# PROC010C_LDO.net
KiCad netlist of a schematic drawn in Altium Designer
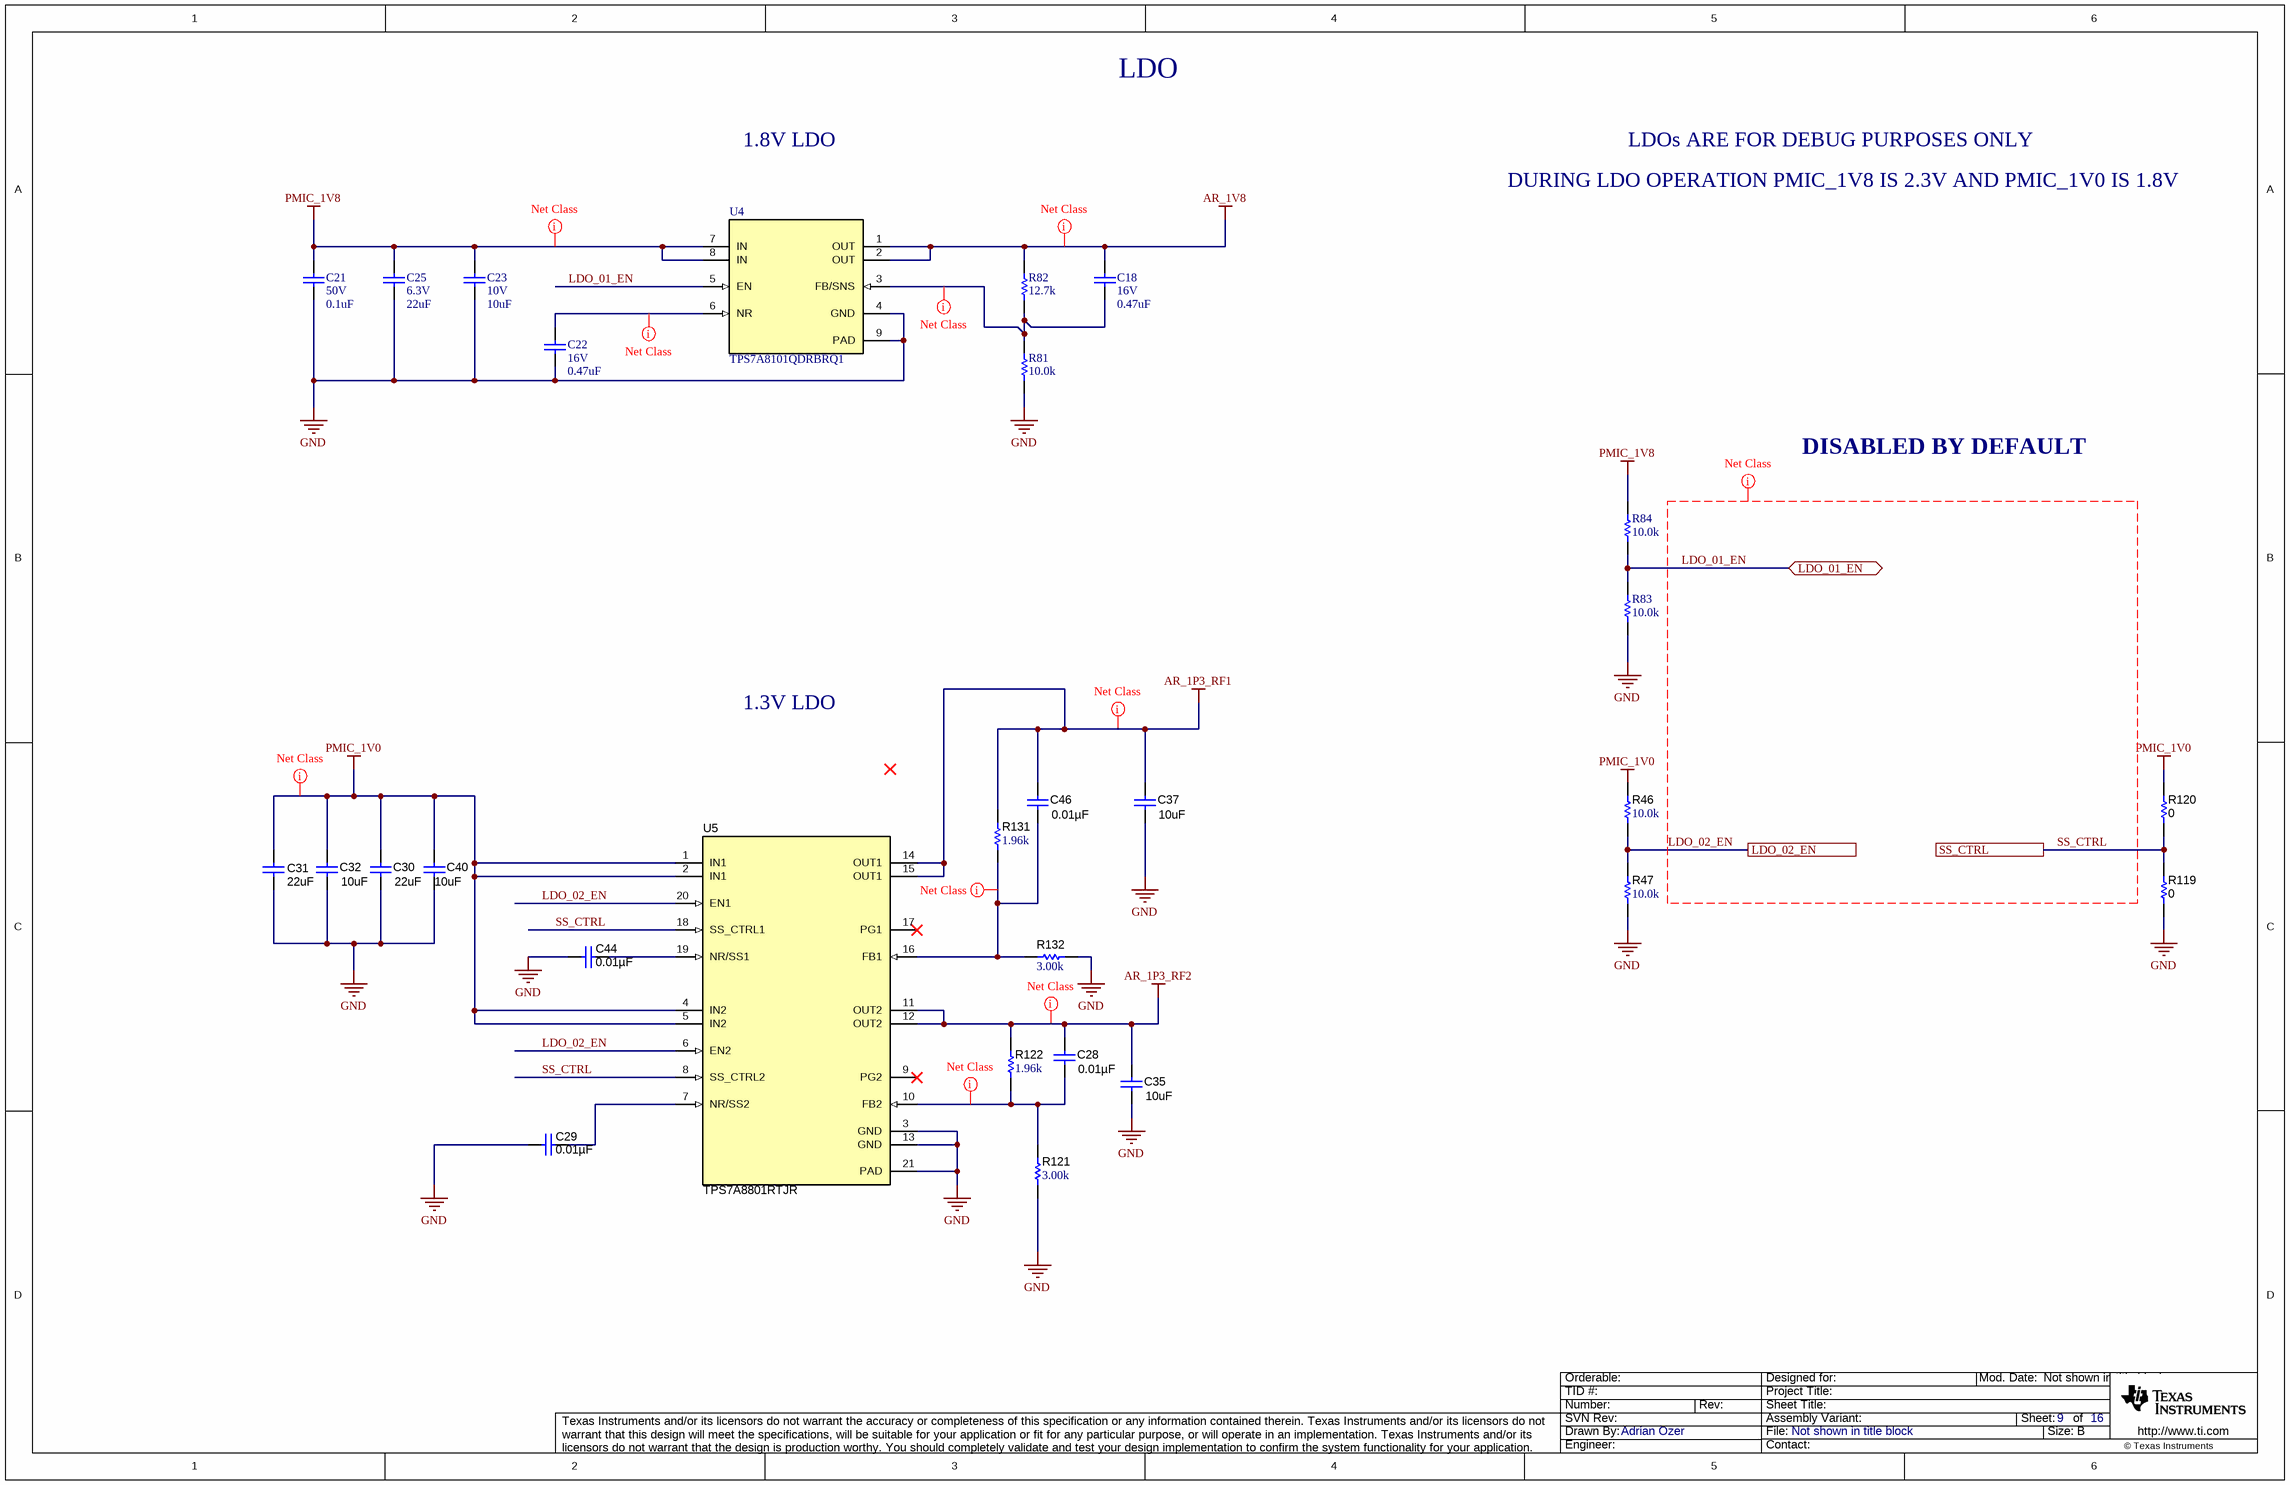
[diagram p0: PROC010C_LDO.SchDoc]

(export (version "E")
  (design (tool "Eeschema 10.0.6"))
  (components
    (comp (ref "C18")
      (value "GCM188R71C474KA55D")
      (footprint "0603")
      (description "CAP, CERM, 0.47 uF, 16 V, +/- 10%, X7R, AEC-Q200 Grade 1, 0603")
      (fields
        (field (name "MANUFACTURER") "MuRata")
        (field (name "VDC_V") "16V")
        (field (name "VALUEDISPLAYED") "0.47uF")
        (field (name "PUBLISHER") "Texas Instruments")
      )
      (libsource (lib "Altium Vault - TI") (part "Capacitor"))
    )
    (comp (ref "C21")
      (value "CGA2B3X7R1H104K050BB")
      (footprint "0402")
      (description "CAP, CERM, 0.1 uF, 50 V, +/- 10%, X7R, AEC-Q200 Grade 1, 0402")
      (fields
        (field (name "MANUFACTURER") "TDK")
        (field (name "VDC_V") "50V")
        (field (name "VALUEDISPLAYED") "0.1uF")
        (field (name "PUBLISHER") "Texas Instruments")
      )
      (libsource (lib "Altium Vault - TI") (part "Capacitor"))
    )
    (comp (ref "C22")
      (value "GCM188R71C474KA55D")
      (footprint "0603")
      (description "CAP, CERM, 0.47 uF, 16 V, +/- 10%, X7R, AEC-Q200 Grade 1, 0603")
      (fields
        (field (name "MANUFACTURER") "MuRata")
        (field (name "VDC_V") "16V")
        (field (name "VALUEDISPLAYED") "0.47uF")
        (field (name "PUBLISHER") "Texas Instruments")
      )
      (libsource (lib "Altium Vault - TI") (part "Capacitor"))
    )
    (comp (ref "C23")
      (value "GCM21BR71A106KE22L")
      (footprint "0805_HV")
      (description "CAP, CERM, 10 uF, 10 V, +/- 10%, X7R, 0805")
      (fields
        (field (name "MANUFACTURER") "MuRata")
        (field (name "VDC_V") "10V")
        (field (name "VALUEDISPLAYED") "10uF")
        (field (name "PUBLISHER") "Texas Instruments")
      )
      (libsource (lib "Altium Vault - TI") (part "Capacitor"))
    )
    (comp (ref "C25")
      (value "CGA5L1X7R0J226M160AC")
      (footprint "1206_180")
      (description "CAP, CERM, 22 uF, 6.3 V, +/- 10%, X7R, AEC-Q200 Grade 1, 1206")
      (fields
        (field (name "MANUFACTURER") "TDK")
        (field (name "VDC_V") "6.3V")
        (field (name "VALUEDISPLAYED") "22uF")
        (field (name "PUBLISHER") "Texas Instruments")
      )
      (libsource (lib "Altium Vault - TI") (part "Capacitor"))
    )
    (comp (ref "C28")
      (value "CGA2B3X8R1H103K050BB")
      (footprint "0402L")
      (description "CAP, CERM, 0.01 µF, 50 V,+/- 10%, X8R, AEC-Q200 Grade 0, 0402")
      (fields (field (name "MANUFACTURER") "TDK") (field (name "VALUEDISPLAYED") "0.01µF"))
      (libsource (lib "Altium Vault - TI") (part "Capacitor"))
    )
    (comp (ref "C29")
      (value "CGA2B3X8R1H103K050BB")
      (footprint "0402L")
      (description "CAP, CERM, 0.01 µF, 50 V,+/- 10%, X8R, AEC-Q200 Grade 0, 0402")
      (fields (field (name "MANUFACTURER") "TDK") (field (name "VALUEDISPLAYED") "0.01µF"))
      (libsource (lib "Altium Vault - TI") (part "Capacitor"))
    )
    (comp (ref "C30")
      (value "CGA5L1X7R0J226M160AC")
      (footprint "1206_180")
      (description "CAP, CERM, 22 uF, 6.3 V, +/- 10%, X7R, AEC-Q200 Grade 1, 1206")
      (fields
        (field (name "MANUFACTURER") "TDK")
        (field (name "VALUEDISPLAYED") "22uF")
        (field (name "PUBLISHER") "Texas Instruments")
      )
      (libsource (lib "Altium Vault - TI") (part "Capacitor"))
    )
    (comp (ref "C31")
      (value "CGA5L1X7R0J226M160AC")
      (footprint "1206_180")
      (description "CAP, CERM, 22 uF, 6.3 V, +/- 10%, X7R, AEC-Q200 Grade 1, 1206")
      (fields
        (field (name "MANUFACTURER") "TDK")
        (field (name "VALUEDISPLAYED") "22uF")
        (field (name "PUBLISHER") "Texas Instruments")
      )
      (libsource (lib "Altium Vault - TI") (part "Capacitor"))
    )
    (comp (ref "C32")
      (value "GCM21BR71A106KE22L")
      (footprint "0805")
      (description "CAP, CERM, 10 uF, 10 V, +/- 10%, X7R, 0805")
      (fields
        (field (name "MANUFACTURER") "MuRata")
        (field (name "VALUEDISPLAYED") "10uF")
        (field (name "PUBLISHER") "Texas Instruments")
      )
      (libsource (lib "Altium Vault - TI") (part "CMP-0008017-2"))
    )
    (comp (ref "C35")
      (value "GCM21BR71A106KE22L")
      (footprint "0805_HV")
      (description "CAP, CERM, 10 uF, 10 V, +/- 10%, X7R, 0805")
      (fields
        (field (name "MANUFACTURER") "MuRata")
        (field (name "VALUEDISPLAYED") "10uF")
        (field (name "PUBLISHER") "Texas Instruments")
      )
      (libsource (lib "Altium Vault - TI") (part "CMP-0008017-2"))
    )
    (comp (ref "C37")
      (value "GCM21BR71A106KE22L")
      (footprint "0805_HV")
      (description "CAP, CERM, 10 uF, 10 V, +/- 10%, X7R, 0805")
      (fields
        (field (name "MANUFACTURER") "MuRata")
        (field (name "VALUEDISPLAYED") "10uF")
        (field (name "PUBLISHER") "Texas Instruments")
      )
      (libsource (lib "Altium Vault - TI") (part "CMP-0008017-2"))
    )
    (comp (ref "C40")
      (value "GCM21BR71A106KE22L")
      (footprint "0805_HV1")
      (description "CAP, CERM, 10 uF, 10 V, +/- 10%, X7R, 0805")
      (fields
        (field (name "MANUFACTURER") "MuRata")
        (field (name "VALUEDISPLAYED") "10uF")
        (field (name "PUBLISHER") "Texas Instruments")
      )
      (libsource (lib "Altium Vault - TI") (part "CMP-0008017-2"))
    )
    (comp (ref "C44")
      (value "CGA2B3X8R1H103K050BB")
      (footprint "0402L")
      (description "CAP, CERM, 0.01 µF, 50 V,+/- 10%, X8R, AEC-Q200 Grade 0, 0402")
      (fields (field (name "MANUFACTURER") "TDK") (field (name "VALUEDISPLAYED") "0.01µF"))
      (libsource (lib "Altium Vault - TI") (part "Capacitor"))
    )
    (comp (ref "C46")
      (value "CGA2B3X8R1H103K050BB")
      (footprint "0402L")
      (description "CAP, CERM, 0.01 µF, 50 V,+/- 10%, X8R, AEC-Q200 Grade 0, 0402")
      (fields (field (name "MANUFACTURER") "TDK") (field (name "VALUEDISPLAYED") "0.01µF"))
      (libsource (lib "Altium Vault - TI") (part "Capacitor"))
    )
    (comp (ref "R46")
      (value "CRCW040210K0FKED")
      (footprint "0402L")
      (description "RES, 10.0 k, 1%, 0.063 W, AEC-Q200 Grade 0, 0402")
      (fields (field (name "MANUFACTURER") "Vishay-Dale") (field (name "VALUEDISPLAYED") "10.0k"))
      (libsource (lib "Altium Vault - TI") (part "Resistor"))
    )
    (comp (ref "R47")
      (value "CRCW040210K0FKED")
      (footprint "0402L")
      (description "RES, 10.0 k, 1%, 0.063 W, AEC-Q200 Grade 0, 0402")
      (fields (field (name "MANUFACTURER") "Vishay-Dale") (field (name "VALUEDISPLAYED") "10.0k"))
      (libsource (lib "Altium Vault - TI") (part "Resistor"))
    )
    (comp (ref "R81")
      (value "CRCW040210K0FKED")
      (footprint "0402L")
      (description "RES, 10.0 k, 1%, 0.063 W, AEC-Q200 Grade 0, 0402")
      (fields (field (name "MANUFACTURER") "Vishay-Dale") (field (name "VALUEDISPLAYED") "10.0k"))
      (libsource (lib "Altium Vault - TI") (part "CMP-0025958-3"))
    )
    (comp (ref "R82")
      (value "CRCW040212K7FKED")
      (footprint "0402L")
      (description "RES, 12.7 k, 1%, 0.063 W, AEC-Q200 Grade 0, 0402")
      (fields (field (name "MANUFACTURER") "Vishay-Dale") (field (name "VALUEDISPLAYED") "12.7k"))
      (libsource (lib "Altium Vault - TI") (part "CMP-0025993-3"))
    )
    (comp (ref "R83")
      (value "CRCW040210K0FKED")
      (footprint "0402")
      (description "RES, 10.0 k, 1%, 0.063 W, AEC-Q200 Grade 0, 0402")
      (fields (field (name "MANUFACTURER") "Vishay-Dale") (field (name "VALUEDISPLAYED") "10.0k"))
      (libsource (lib "Altium Vault - TI") (part "Resistor"))
    )
    (comp (ref "R84")
      (value "CRCW040210K0FKED")
      (footprint "0402")
      (description "RES, 10.0 k, 1%, 0.063 W, AEC-Q200 Grade 0, 0402")
      (fields (field (name "MANUFACTURER") "Vishay-Dale") (field (name "VALUEDISPLAYED") "10.0k"))
      (libsource (lib "Altium Vault - TI") (part "Resistor"))
    )
    (comp (ref "R119")
      (value "ERJ-2GE0R00X")
      (footprint "0402L")
      (description "RES, 0, 5%, 0.063 W, 0402")
      (fields
        (field (name "MANUFACTURER") "Panasonic")
        (field (name "VALUEDISPLAYED") "0")
        (field (name "PUBLISHER") "Texas Instruments")
      )
      (libsource (lib "Altium Vault - TI") (part "Resistor"))
    )
    (comp (ref "R120")
      (value "ERJ-2GE0R00X")
      (footprint "0402L")
      (description "RES, 0, 5%, 0.063 W, 0402")
      (fields
        (field (name "MANUFACTURER") "Panasonic")
        (field (name "VALUEDISPLAYED") "0")
        (field (name "PUBLISHER") "Texas Instruments")
      )
      (libsource (lib "Altium Vault - TI") (part "CMP-0026992-2"))
    )
    (comp (ref "R121")
      (value "CRCW04023K00FKED")
      (footprint "0402L")
      (description "RES, 3.00 k, 1%, 0.063 W, AEC-Q200 Grade 0, 0402")
      (fields (field (name "MANUFACTURER") "Vishay-Dale") (field (name "VALUEDISPLAYED") "3.00k"))
      (libsource (lib "Altium Vault - TI") (part "Resistor"))
    )
    (comp (ref "R122")
      (value "CRCW04021K96FKED")
      (footprint "0402L")
      (description "RES, 1.96 k, 1%, 0.063 W, AEC-Q200 Grade 0, 0402")
      (fields (field (name "MANUFACTURER") "Vishay-Dale") (field (name "VALUEDISPLAYED") "1.96k"))
      (libsource (lib "Altium Vault - TI") (part "Resistor"))
    )
    (comp (ref "R131")
      (value "CRCW04021K96FKED")
      (footprint "0402L")
      (description "RES, 1.96 k, 1%, 0.063 W, AEC-Q200 Grade 0, 0402")
      (fields (field (name "MANUFACTURER") "Vishay-Dale") (field (name "VALUEDISPLAYED") "1.96k"))
      (libsource (lib "Altium Vault - TI") (part "Resistor"))
    )
    (comp (ref "R132")
      (value "CRCW04023K00FKED")
      (footprint "0402L")
      (description "RES, 3.00 k, 1%, 0.063 W, AEC-Q200 Grade 0, 0402")
      (fields (field (name "MANUFACTURER") "Vishay-Dale") (field (name "VALUEDISPLAYED") "3.00k"))
      (libsource (lib "Altium Vault - TI") (part "Resistor"))
    )
    (comp (ref "U4")
      (value "TPS7A8101QDRBRQ1")
      (footprint "DRB0008A")
      (fields
        (field (name "MANUFACTURER") "Texas Instruments")
        (field (name "PARTNUMBER") "TPS7A8101QDRBRQ1")
        (field (name "PUBLISHER") "Texas Instruments")
      )
      (libsource (lib "Altium Vault - TI") (part "TPS7A80xx"))
    )
    (comp (ref "U5")
      (value "TPS7A8801RTJR")
      (footprint "RTJ0020D")
      (description "Dual, 1-A, Low Noise (3.8-uVRMS), LDO Voltage Regulator, RTJ0020D (WQFN-20)")
      (fields
        (field (name "ALTERNATE PARTNUMBER") "TPS7A8801RTJT")
        (field (name "MANUFACTURER") "Texas Instruments")
        (field (name "PARTNUMBER") "TPS7A8801RTJR")
        (field (name "PUBLISHER") "Texas Instruments")
      )
      (libsource (lib "Altium Vault - TI") (part "TPS7A8801"))
    )
  )
  (nets
    (net (code "1") (name "/LDO_01_EN") (class "Default")
      (node (ref "R83") (pin "2") (pinfunction "2_2") (pintype "passive"))
      (node (ref "R84") (pin "1") (pinfunction "1_1") (pintype "passive"))
      (node (ref "U4") (pin "5") (pinfunction "EN_5") (pintype "input"))
    )
    (net (code "2") (name "/LDO_02_EN") (class "Default")
      (node (ref "R46") (pin "2") (pinfunction "2_2") (pintype "passive"))
      (node (ref "R47") (pin "1") (pinfunction "1_1") (pintype "passive"))
      (node (ref "U5") (pin "20") (pinfunction "EN1_20") (pintype "input"))
      (node (ref "U5") (pin "6") (pinfunction "EN2_6") (pintype "input"))
    )
    (net (code "3") (name "/SS_CTRL") (class "Default")
      (node (ref "R119") (pin "2") (pinfunction "2_2") (pintype "passive"))
      (node (ref "R120") (pin "1") (pinfunction "1_1") (pintype "passive"))
      (node (ref "U5") (pin "18") (pinfunction "SS_CTRL1_18") (pintype "input"))
      (node (ref "U5") (pin "8") (pinfunction "SS_CTRL2_8") (pintype "input"))
    )
    (net (code "4") (name "AR_1P3_RF1") (class "Default")
      (node (ref "C37") (pin "2") (pinfunction "2_2") (pintype "passive"))
      (node (ref "C46") (pin "2") (pinfunction "2_2") (pintype "passive"))
      (node (ref "R131") (pin "2") (pinfunction "2_2") (pintype "passive"))
      (node (ref "U5") (pin "14") (pinfunction "OUT1_14") (pintype "power_in"))
      (node (ref "U5") (pin "15") (pinfunction "OUT1_15") (pintype "power_in"))
    )
    (net (code "5") (name "AR_1P3_RF2") (class "Default")
      (node (ref "C28") (pin "2") (pinfunction "2_2") (pintype "passive"))
      (node (ref "C35") (pin "2") (pinfunction "2_2") (pintype "passive"))
      (node (ref "R122") (pin "2") (pinfunction "2_2") (pintype "passive"))
      (node (ref "U5") (pin "11") (pinfunction "OUT2_11") (pintype "power_in"))
      (node (ref "U5") (pin "12") (pinfunction "OUT2_12") (pintype "power_in"))
    )
    (net (code "6") (name "AR_1V8") (class "Default")
      (node (ref "C18") (pin "1") (pinfunction "1_1") (pintype "passive"))
      (node (ref "R82") (pin "2") (pinfunction "2_2") (pintype "passive"))
      (node (ref "U4") (pin "1") (pinfunction "OUT_1") (pintype "power_in"))
      (node (ref "U4") (pin "2") (pinfunction "OUT_2") (pintype "power_in"))
    )
    (net (code "7") (name "GND") (class "Default")
      (node (ref "C21") (pin "2") (pinfunction "2_2") (pintype "passive"))
      (node (ref "C22") (pin "2") (pinfunction "2_2") (pintype "passive"))
      (node (ref "C23") (pin "2") (pinfunction "2_2") (pintype "passive"))
      (node (ref "C25") (pin "2") (pinfunction "2_2") (pintype "passive"))
      (node (ref "C29") (pin "1") (pinfunction "1_1") (pintype "passive"))
      (node (ref "C30") (pin "1") (pinfunction "1_1") (pintype "passive"))
      (node (ref "C31") (pin "1") (pinfunction "1_1") (pintype "passive"))
      (node (ref "C32") (pin "1") (pinfunction "1_1") (pintype "passive"))
      (node (ref "C35") (pin "1") (pinfunction "1_1") (pintype "passive"))
      (node (ref "C37") (pin "1") (pinfunction "1_1") (pintype "passive"))
      (node (ref "C40") (pin "1") (pinfunction "1_1") (pintype "passive"))
      (node (ref "C44") (pin "1") (pinfunction "1_1") (pintype "passive"))
      (node (ref "R119") (pin "1") (pinfunction "1_1") (pintype "passive"))
      (node (ref "R121") (pin "1") (pinfunction "1_1") (pintype "passive"))
      (node (ref "R132") (pin "1") (pinfunction "1_1") (pintype "passive"))
      (node (ref "R47") (pin "2") (pinfunction "2_2") (pintype "passive"))
      (node (ref "R81") (pin "1") (pinfunction "1_1") (pintype "passive"))
      (node (ref "R83") (pin "1") (pinfunction "1_1") (pintype "passive"))
      (node (ref "U4") (pin "4") (pinfunction "GND_4") (pintype "power_in"))
      (node (ref "U4") (pin "9") (pinfunction "PAD_9") (pintype "passive"))
      (node (ref "U5") (pin "13") (pinfunction "GND_13") (pintype "power_in"))
      (node (ref "U5") (pin "21") (pinfunction "PAD_21") (pintype "power_in"))
      (node (ref "U5") (pin "3") (pinfunction "GND_3") (pintype "power_in"))
    )
    (net (code "8") (name "Net-(U4-FB{slash}SNS)") (class "Default")
      (node (ref "C18") (pin "2") (pinfunction "2_2") (pintype "passive"))
      (node (ref "R81") (pin "2") (pinfunction "2_2") (pintype "passive"))
      (node (ref "R82") (pin "1") (pinfunction "1_1") (pintype "passive"))
      (node (ref "U4") (pin "3") (pinfunction "FB/SNS_3") (pintype "input"))
    )
    (net (code "9") (name "Net-(U4-NR)") (class "Default")
      (node (ref "C22") (pin "1") (pinfunction "1_1") (pintype "passive"))
      (node (ref "U4") (pin "6") (pinfunction "NR_6") (pintype "input"))
    )
    (net (code "10") (name "Net-(U5-FB1)") (class "Default")
      (node (ref "C46") (pin "1") (pinfunction "1_1") (pintype "passive"))
      (node (ref "R131") (pin "1") (pinfunction "1_1") (pintype "passive"))
      (node (ref "R132") (pin "2") (pinfunction "2_2") (pintype "passive"))
      (node (ref "U5") (pin "16") (pinfunction "FB1_16") (pintype "input"))
    )
    (net (code "11") (name "Net-(U5-FB2)") (class "Default")
      (node (ref "C28") (pin "1") (pinfunction "1_1") (pintype "passive"))
      (node (ref "R121") (pin "2") (pinfunction "2_2") (pintype "passive"))
      (node (ref "R122") (pin "1") (pinfunction "1_1") (pintype "passive"))
      (node (ref "U5") (pin "10") (pinfunction "FB2_10") (pintype "input"))
    )
    (net (code "12") (name "Net-(U5-NR{slash}SS1)") (class "Default")
      (node (ref "C44") (pin "2") (pinfunction "2_2") (pintype "passive"))
      (node (ref "U5") (pin "19") (pinfunction "NR/SS1_19") (pintype "input"))
    )
    (net (code "13") (name "Net-(U5-NR{slash}SS2)") (class "Default")
      (node (ref "C29") (pin "2") (pinfunction "2_2") (pintype "passive"))
      (node (ref "U5") (pin "7") (pinfunction "NR/SS2_7") (pintype "input"))
    )
    (net (code "14") (name "PMIC_1V0") (class "Default")
      (node (ref "C30") (pin "2") (pinfunction "2_2") (pintype "passive"))
      (node (ref "C31") (pin "2") (pinfunction "2_2") (pintype "passive"))
      (node (ref "C32") (pin "2") (pinfunction "2_2") (pintype "passive"))
      (node (ref "C40") (pin "2") (pinfunction "2_2") (pintype "passive"))
      (node (ref "R120") (pin "2") (pinfunction "2_2") (pintype "passive"))
      (node (ref "R46") (pin "1") (pinfunction "1_1") (pintype "passive"))
      (node (ref "U5") (pin "1") (pinfunction "IN1_1") (pintype "power_in"))
      (node (ref "U5") (pin "2") (pinfunction "IN1_2") (pintype "power_in"))
      (node (ref "U5") (pin "4") (pinfunction "IN2_4") (pintype "power_in"))
      (node (ref "U5") (pin "5") (pinfunction "IN2_5") (pintype "power_in"))
    )
    (net (code "15") (name "PMIC_1V8") (class "Default")
      (node (ref "C21") (pin "1") (pinfunction "1_1") (pintype "passive"))
      (node (ref "C23") (pin "1") (pinfunction "1_1") (pintype "passive"))
      (node (ref "C25") (pin "1") (pinfunction "1_1") (pintype "passive"))
      (node (ref "R84") (pin "2") (pinfunction "2_2") (pintype "passive"))
      (node (ref "U4") (pin "7") (pinfunction "IN_7") (pintype "power_in"))
      (node (ref "U4") (pin "8") (pinfunction "IN_8") (pintype "power_in"))
    )
    (net (code "16") (name "unconnected-(U5-PG1-Pad17)") (class "Default")
      (node (ref "U5") (pin "17") (pinfunction "PG1_17") (pintype "open_collector+no_connect"))
    )
    (net (code "17") (name "unconnected-(U5-PG2-Pad9)") (class "Default")
      (node (ref "U5") (pin "9") (pinfunction "PG2_9") (pintype "open_collector+no_connect"))
    )
  )
)
